# RC_Receiver.net
KiCad netlist of a schematic drawn in EasyEDA Pro
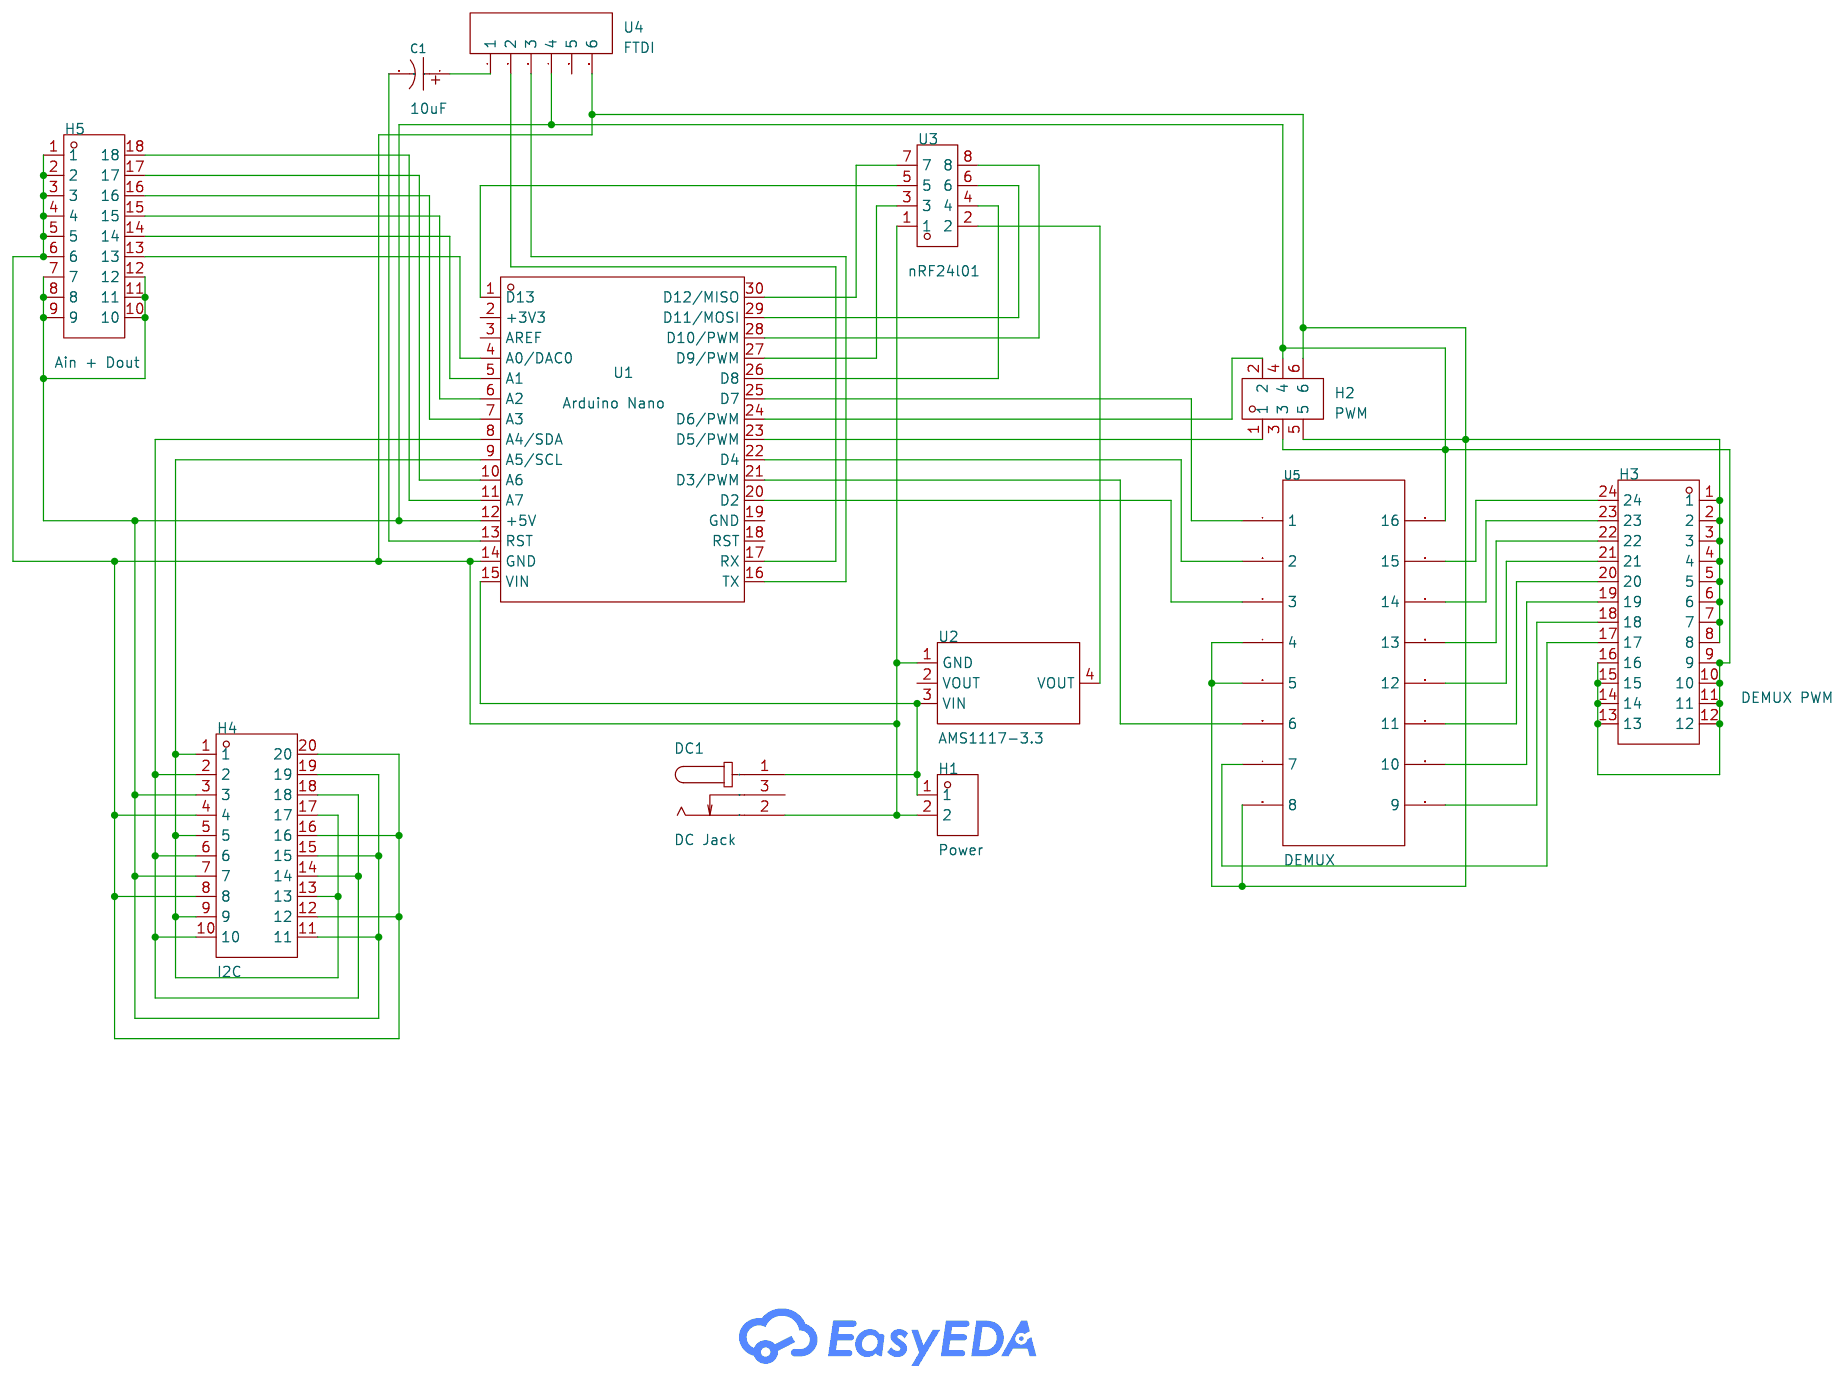
[diagram p0: schematic sheet]

(export (version "E")
  (design (tool "Eeschema 10.0.6"))
  (components
    (comp (ref "C1")
      (value "10uF")
      (footprint "easyedapro:CAP-TH_BD5.0-P2.00-D0.8-FD")
      (fields (field (name "Manufacturer Part") "RD1H106M05011PC") (field (name "Manufacturer") "SAMWHA(三和)"))
      (libsource (lib "easyedapro") (part "RD1H106M05011PC"))
    )
    (comp (ref "DC1")
      (value "DC Jack")
      (footprint "easyedapro:DC-IN-TH_DC-005-5A-2.0")
      (fields (field (name "Manufacturer") "XKB Connection(中国星坤)"))
      (libsource (lib "easyedapro") (part "DC-005-5A-2.0"))
    )
    (comp (ref "H1")
      (value "Power")
      (footprint "easyedapro:HDR-TH_2P-P2.54-V-M_5")
      (fields (field (name "Manufacturer") "HCTL(华灿天禄)"))
      (libsource (lib "easyedapro") (part "PZ254-1-02-Z-C"))
    )
    (comp (ref "H2")
      (value "PWM")
      (footprint "easyedapro:HDR-TH_6P-P2.54-V-M-R2-C3-S2.54")
      (fields (field (name "Manufacturer") "XFCN(兴飞)"))
      (libsource (lib "easyedapro") (part "PZ254V-12-6P"))
    )
    (comp (ref "H3")
      (value "DEMUX PWM")
      (footprint "easyedapro:HDR-TH_24P-P2.54-V-M-R3-C8-S2.54_1")
      (fields (field (name "Manufacturer") "hanxia(韩下)"))
      (libsource (lib "easyedapro") (part "HX PZ2.54-3X8P ZZ"))
    )
    (comp (ref "H4")
      (value "I2C")
      (footprint "easyedapro:HDR-TH_20P-P2.54-V-M-R4-C5-S2.54")
      (fields (field (name "Manufacturer") "hanxia(韩下)"))
      (libsource (lib "easyedapro") (part "HX PZ2.54-4X5P ZZ"))
    )
    (comp (ref "H5")
      (value "Ain + Dout")
      (footprint "easyedapro:CONN-TH_HX-PZ2.54-3X6P-ZZ")
      (fields (field (name "Manufacturer") "hanxia(韩下)"))
      (libsource (lib "easyedapro") (part "HX PZ2.54-3X6P ZZ"))
    )
    (comp (ref "U1")
      (value "Arduino Nano")
      (footprint "easyedapro:MOD-TH_ABX00028")
      (fields (field (name "Manufacturer") "arduino"))
      (libsource (lib "easyedapro") (part "ABX00028"))
    )
    (comp (ref "U2")
      (value "AMS1117-3.3")
      (footprint "easyedapro:SOT-223-3_L6.5-W3.4-P2.30-LS7.0-BR")
      (fields (field (name "Manufacturer") "AMS"))
      (libsource (lib "easyedapro") (part "AMS1117-3.3"))
    )
    (comp (ref "U3")
      (value "nRF24l01")
      (footprint "easyedapro:HDR-TH_8P-P2.54-V-F-R2-C4-S2.54")
      (fields (field (name "Manufacturer") "ZHOURI(洲日)"))
      (libsource (lib "easyedapro") (part "2.54-2*4"))
    )
    (comp (ref "U4")
      (value "FTDI")
      (footprint "easyedapro:HDR-TH_6P-P2.54-V-M-1")
      (fields (field (name "Manufacturer") "BOOMELE(博穆精密)"))
      (libsource (lib "easyedapro") (part "Header-Male-2.54_1x6"))
    )
    (comp (ref "U5")
      (value "DEMUX")
      (footprint "easyedapro:DIP-16_L20.3-W10.2-P2.54-LS7.6-BL-2")
      (description "IC Type:DIP Pitch:2.54mm Row Spacing:7.62mm Number of Positions:16P Contact Plating:Tin")
      (fields (field (name "Manufacturer") "CONNFLY"))
      (libsource (lib "easyedapro") (part "DS1009-16AT1NX-0A2"))
    )
  )
  (nets
    (net (code "1") (name "Net-(C1-Pad1)") (class "Default")
      (node (ref "C1") (pin "1") (pinfunction "1_1") (pintype "input"))
      (node (ref "U4") (pin "1") (pinfunction "1_1") (pintype "input"))
    )
    (net (code "2") (name "Net-(C1-Pad2)") (class "Default")
      (node (ref "C1") (pin "2") (pinfunction "2_2") (pintype "input"))
      (node (ref "U1") (pin "13") (pinfunction "RST_13") (pintype "unspecified"))
    )
    (net (code "3") (name "Net-(H3-Pad17)") (class "Default")
      (node (ref "H3") (pin "17") (pinfunction "17_17") (pintype "unspecified"))
      (node (ref "U5") (pin "7") (pinfunction "7_7") (pintype "input"))
    )
    (net (code "4") (name "Net-(H3-Pad18)") (class "Default")
      (node (ref "H3") (pin "18") (pinfunction "18_18") (pintype "unspecified"))
      (node (ref "U5") (pin "9") (pinfunction "9_9") (pintype "input"))
    )
    (net (code "5") (name "Net-(H3-Pad19)") (class "Default")
      (node (ref "H3") (pin "19") (pinfunction "19_19") (pintype "unspecified"))
      (node (ref "U5") (pin "10") (pinfunction "10_10") (pintype "input"))
    )
    (net (code "6") (name "Net-(H3-Pad20)") (class "Default")
      (node (ref "H3") (pin "20") (pinfunction "20_20") (pintype "unspecified"))
      (node (ref "U5") (pin "11") (pinfunction "11_11") (pintype "input"))
    )
    (net (code "7") (name "Net-(H3-Pad21)") (class "Default")
      (node (ref "H3") (pin "21") (pinfunction "21_21") (pintype "unspecified"))
      (node (ref "U5") (pin "12") (pinfunction "12_12") (pintype "input"))
    )
    (net (code "8") (name "Net-(H3-Pad22)") (class "Default")
      (node (ref "H3") (pin "22") (pinfunction "22_22") (pintype "unspecified"))
      (node (ref "U5") (pin "13") (pinfunction "13_13") (pintype "input"))
    )
    (net (code "9") (name "Net-(H3-Pad23)") (class "Default")
      (node (ref "H3") (pin "23") (pinfunction "23_23") (pintype "unspecified"))
      (node (ref "U5") (pin "14") (pinfunction "14_14") (pintype "input"))
    )
    (net (code "10") (name "Net-(H3-Pad24)") (class "Default")
      (node (ref "H3") (pin "24") (pinfunction "24_24") (pintype "unspecified"))
      (node (ref "U5") (pin "15") (pinfunction "15_15") (pintype "input"))
    )
    (net (code "11") (name "Net-(U1-+5V)") (class "Default")
      (node (ref "H2") (pin "3") (pinfunction "3_3") (pintype "unspecified"))
      (node (ref "H2") (pin "4") (pinfunction "4_4") (pintype "unspecified"))
      (node (ref "H3") (pin "10") (pinfunction "10_10") (pintype "unspecified"))
      (node (ref "H3") (pin "11") (pinfunction "11_11") (pintype "unspecified"))
      (node (ref "H3") (pin "12") (pinfunction "12_12") (pintype "unspecified"))
      (node (ref "H3") (pin "13") (pinfunction "13_13") (pintype "unspecified"))
      (node (ref "H3") (pin "14") (pinfunction "14_14") (pintype "unspecified"))
      (node (ref "H3") (pin "15") (pinfunction "15_15") (pintype "unspecified"))
      (node (ref "H3") (pin "16") (pinfunction "16_16") (pintype "unspecified"))
      (node (ref "H3") (pin "9") (pinfunction "9_9") (pintype "unspecified"))
      (node (ref "H4") (pin "11") (pinfunction "11_11") (pintype "unspecified"))
      (node (ref "H4") (pin "15") (pinfunction "15_15") (pintype "unspecified"))
      (node (ref "H4") (pin "19") (pinfunction "19_19") (pintype "unspecified"))
      (node (ref "H4") (pin "3") (pinfunction "3_3") (pintype "unspecified"))
      (node (ref "H4") (pin "7") (pinfunction "7_7") (pintype "unspecified"))
      (node (ref "H5") (pin "10") (pinfunction "10_10") (pintype "unspecified"))
      (node (ref "H5") (pin "11") (pinfunction "11_11") (pintype "unspecified"))
      (node (ref "H5") (pin "12") (pinfunction "12_12") (pintype "unspecified"))
      (node (ref "H5") (pin "7") (pinfunction "7_7") (pintype "unspecified"))
      (node (ref "H5") (pin "8") (pinfunction "8_8") (pintype "unspecified"))
      (node (ref "H5") (pin "9") (pinfunction "9_9") (pintype "unspecified"))
      (node (ref "U1") (pin "12") (pinfunction "+5V_12") (pintype "unspecified"))
      (node (ref "U4") (pin "4") (pinfunction "4_4") (pintype "input"))
      (node (ref "U5") (pin "16") (pinfunction "16_16") (pintype "input"))
    )
    (net (code "12") (name "Net-(U1-A0{slash}DAC0)") (class "Default")
      (node (ref "H5") (pin "13") (pinfunction "13_13") (pintype "unspecified"))
      (node (ref "U1") (pin "4") (pinfunction "A0/DAC0_4") (pintype "unspecified"))
    )
    (net (code "13") (name "Net-(U1-A1)") (class "Default")
      (node (ref "H5") (pin "14") (pinfunction "14_14") (pintype "unspecified"))
      (node (ref "U1") (pin "5") (pinfunction "A1_5") (pintype "unspecified"))
    )
    (net (code "14") (name "Net-(U1-A2)") (class "Default")
      (node (ref "H5") (pin "15") (pinfunction "15_15") (pintype "unspecified"))
      (node (ref "U1") (pin "6") (pinfunction "A2_6") (pintype "unspecified"))
    )
    (net (code "15") (name "Net-(U1-A3)") (class "Default")
      (node (ref "H5") (pin "16") (pinfunction "16_16") (pintype "unspecified"))
      (node (ref "U1") (pin "7") (pinfunction "A3_7") (pintype "unspecified"))
    )
    (net (code "16") (name "Net-(U1-A4{slash}SDA)") (class "Default")
      (node (ref "H4") (pin "10") (pinfunction "10_10") (pintype "unspecified"))
      (node (ref "H4") (pin "14") (pinfunction "14_14") (pintype "unspecified"))
      (node (ref "H4") (pin "18") (pinfunction "18_18") (pintype "unspecified"))
      (node (ref "H4") (pin "2") (pinfunction "2_2") (pintype "unspecified"))
      (node (ref "H4") (pin "6") (pinfunction "6_6") (pintype "unspecified"))
      (node (ref "U1") (pin "8") (pinfunction "A4/SDA_8") (pintype "unspecified"))
    )
    (net (code "17") (name "Net-(U1-A5{slash}SCL)") (class "Default")
      (node (ref "H4") (pin "1") (pinfunction "1_1") (pintype "unspecified"))
      (node (ref "H4") (pin "13") (pinfunction "13_13") (pintype "unspecified"))
      (node (ref "H4") (pin "17") (pinfunction "17_17") (pintype "unspecified"))
      (node (ref "H4") (pin "5") (pinfunction "5_5") (pintype "unspecified"))
      (node (ref "H4") (pin "9") (pinfunction "9_9") (pintype "unspecified"))
      (node (ref "U1") (pin "9") (pinfunction "A5/SCL_9") (pintype "unspecified"))
    )
    (net (code "18") (name "Net-(U1-A6)") (class "Default")
      (node (ref "H5") (pin "17") (pinfunction "17_17") (pintype "unspecified"))
      (node (ref "U1") (pin "10") (pinfunction "A6_10") (pintype "unspecified"))
    )
    (net (code "19") (name "Net-(U1-A7)") (class "Default")
      (node (ref "H5") (pin "18") (pinfunction "18_18") (pintype "unspecified"))
      (node (ref "U1") (pin "11") (pinfunction "A7_11") (pintype "unspecified"))
    )
    (net (code "20") (name "Net-(U1-D2)") (class "Default")
      (node (ref "U1") (pin "20") (pinfunction "D2_20") (pintype "unspecified"))
      (node (ref "U5") (pin "3") (pinfunction "3_3") (pintype "input"))
    )
    (net (code "21") (name "Net-(U1-D3{slash}PWM)") (class "Default")
      (node (ref "U1") (pin "21") (pinfunction "D3/PWM_21") (pintype "unspecified"))
      (node (ref "U5") (pin "6") (pinfunction "6_6") (pintype "input"))
    )
    (net (code "22") (name "Net-(U1-D4)") (class "Default")
      (node (ref "U1") (pin "22") (pinfunction "D4_22") (pintype "unspecified"))
      (node (ref "U5") (pin "2") (pinfunction "2_2") (pintype "input"))
    )
    (net (code "23") (name "Net-(U1-D5{slash}PWM)") (class "Default")
      (node (ref "H2") (pin "1") (pinfunction "1_1") (pintype "unspecified"))
      (node (ref "U1") (pin "23") (pinfunction "D5/PWM_23") (pintype "unspecified"))
    )
    (net (code "24") (name "Net-(U1-D6{slash}PWM)") (class "Default")
      (node (ref "H2") (pin "2") (pinfunction "2_2") (pintype "unspecified"))
      (node (ref "U1") (pin "24") (pinfunction "D6/PWM_24") (pintype "unspecified"))
    )
    (net (code "25") (name "Net-(U1-D7)") (class "Default")
      (node (ref "U1") (pin "25") (pinfunction "D7_25") (pintype "unspecified"))
      (node (ref "U5") (pin "1") (pinfunction "1_1") (pintype "input"))
    )
    (net (code "26") (name "Net-(U1-D8)") (class "Default")
      (node (ref "U1") (pin "26") (pinfunction "D8_26") (pintype "unspecified"))
      (node (ref "U3") (pin "4") (pinfunction "4_4") (pintype "unspecified"))
    )
    (net (code "27") (name "Net-(U1-D9{slash}PWM)") (class "Default")
      (node (ref "U1") (pin "27") (pinfunction "D9/PWM_27") (pintype "unspecified"))
      (node (ref "U3") (pin "3") (pinfunction "3_3") (pintype "unspecified"))
    )
    (net (code "28") (name "Net-(U1-D10{slash}PWM)") (class "Default")
      (node (ref "U1") (pin "28") (pinfunction "D10/PWM_28") (pintype "unspecified"))
      (node (ref "U3") (pin "8") (pinfunction "8_8") (pintype "unspecified"))
    )
    (net (code "29") (name "Net-(U1-D11{slash}MOSI)") (class "Default")
      (node (ref "U1") (pin "29") (pinfunction "D11/MOSI_29") (pintype "unspecified"))
      (node (ref "U3") (pin "6") (pinfunction "6_6") (pintype "unspecified"))
    )
    (net (code "30") (name "Net-(U1-D12{slash}MISO)") (class "Default")
      (node (ref "U1") (pin "30") (pinfunction "D12/MISO_30") (pintype "unspecified"))
      (node (ref "U3") (pin "7") (pinfunction "7_7") (pintype "unspecified"))
    )
    (net (code "31") (name "Net-(U1-D13)") (class "Default")
      (node (ref "U1") (pin "1") (pinfunction "D13_1") (pintype "unspecified"))
      (node (ref "U3") (pin "5") (pinfunction "5_5") (pintype "unspecified"))
    )
    (net (code "32") (name "Net-(U1-RX)") (class "Default")
      (node (ref "U1") (pin "17") (pinfunction "RX_17") (pintype "unspecified"))
      (node (ref "U4") (pin "2") (pinfunction "2_2") (pintype "input"))
    )
    (net (code "33") (name "Net-(U1-TX)") (class "Default")
      (node (ref "U1") (pin "16") (pinfunction "TX_16") (pintype "unspecified"))
      (node (ref "U4") (pin "3") (pinfunction "3_3") (pintype "input"))
    )
    (net (code "34") (name "Net-(U1-VIN)") (class "Default")
      (node (ref "DC1") (pin "1") (pinfunction "1_1") (pintype "unspecified"))
      (node (ref "H1") (pin "1") (pinfunction "1_1") (pintype "unspecified"))
      (node (ref "U1") (pin "15") (pinfunction "VIN_15") (pintype "unspecified"))
      (node (ref "U2") (pin "3") (pinfunction "VIN_3") (pintype "unspecified"))
    )
    (net (code "35") (name "Net-(U2-GND)") (class "Default")
      (node (ref "DC1") (pin "2") (pinfunction "2_2") (pintype "unspecified"))
      (node (ref "H1") (pin "2") (pinfunction "2_2") (pintype "unspecified"))
      (node (ref "H2") (pin "5") (pinfunction "5_5") (pintype "unspecified"))
      (node (ref "H2") (pin "6") (pinfunction "6_6") (pintype "unspecified"))
      (node (ref "H3") (pin "1") (pinfunction "1_1") (pintype "unspecified"))
      (node (ref "H3") (pin "2") (pinfunction "2_2") (pintype "unspecified"))
      (node (ref "H3") (pin "3") (pinfunction "3_3") (pintype "unspecified"))
      (node (ref "H3") (pin "4") (pinfunction "4_4") (pintype "unspecified"))
      (node (ref "H3") (pin "5") (pinfunction "5_5") (pintype "unspecified"))
      (node (ref "H3") (pin "6") (pinfunction "6_6") (pintype "unspecified"))
      (node (ref "H3") (pin "7") (pinfunction "7_7") (pintype "unspecified"))
      (node (ref "H3") (pin "8") (pinfunction "8_8") (pintype "unspecified"))
      (node (ref "H4") (pin "12") (pinfunction "12_12") (pintype "unspecified"))
      (node (ref "H4") (pin "16") (pinfunction "16_16") (pintype "unspecified"))
      (node (ref "H4") (pin "20") (pinfunction "20_20") (pintype "unspecified"))
      (node (ref "H4") (pin "4") (pinfunction "4_4") (pintype "unspecified"))
      (node (ref "H4") (pin "8") (pinfunction "8_8") (pintype "unspecified"))
      (node (ref "H5") (pin "1") (pinfunction "1_1") (pintype "unspecified"))
      (node (ref "H5") (pin "2") (pinfunction "2_2") (pintype "unspecified"))
      (node (ref "H5") (pin "3") (pinfunction "3_3") (pintype "unspecified"))
      (node (ref "H5") (pin "4") (pinfunction "4_4") (pintype "unspecified"))
      (node (ref "H5") (pin "5") (pinfunction "5_5") (pintype "unspecified"))
      (node (ref "H5") (pin "6") (pinfunction "6_6") (pintype "unspecified"))
      (node (ref "U1") (pin "14") (pinfunction "GND_14") (pintype "unspecified"))
      (node (ref "U2") (pin "1") (pinfunction "GND_1") (pintype "unspecified"))
      (node (ref "U3") (pin "1") (pinfunction "1_1") (pintype "unspecified"))
      (node (ref "U4") (pin "6") (pinfunction "6_6") (pintype "input"))
      (node (ref "U5") (pin "4") (pinfunction "4_4") (pintype "input"))
      (node (ref "U5") (pin "5") (pinfunction "5_5") (pintype "input"))
      (node (ref "U5") (pin "8") (pinfunction "8_8") (pintype "input"))
    )
    (net (code "36") (name "Net-(U2-VOUT-Pad4)") (class "Default")
      (node (ref "U2") (pin "4") (pinfunction "VOUT_4") (pintype "unspecified"))
      (node (ref "U3") (pin "2") (pinfunction "2_2") (pintype "unspecified"))
    )
    (net (code "37") (name "unconnected-(DC1-Pad3)") (class "Default")
      (node (ref "DC1") (pin "3") (pinfunction "3_3") (pintype "unspecified"))
    )
    (net (code "38") (name "unconnected-(U1-+3V3-Pad2)") (class "Default")
      (node (ref "U1") (pin "2") (pinfunction "+3V3_2") (pintype "unspecified"))
    )
    (net (code "39") (name "unconnected-(U1-AREF-Pad3)") (class "Default")
      (node (ref "U1") (pin "3") (pinfunction "AREF_3") (pintype "unspecified"))
    )
    (net (code "40") (name "unconnected-(U1-GND-Pad19)") (class "Default")
      (node (ref "U1") (pin "19") (pinfunction "GND_19") (pintype "unspecified"))
    )
    (net (code "41") (name "unconnected-(U1-RST-Pad18)") (class "Default")
      (node (ref "U1") (pin "18") (pinfunction "RST_18") (pintype "unspecified"))
    )
    (net (code "42") (name "unconnected-(U2-VOUT-Pad2)") (class "Default")
      (node (ref "U2") (pin "2") (pinfunction "VOUT_2") (pintype "unspecified"))
    )
    (net (code "43") (name "unconnected-(U4-Pad5)") (class "Default")
      (node (ref "U4") (pin "5") (pinfunction "5_5") (pintype "input"))
    )
  )
)
